# TapuinoNext-Micro.net
KiCad netlist of a schematic drawn in EAGLE
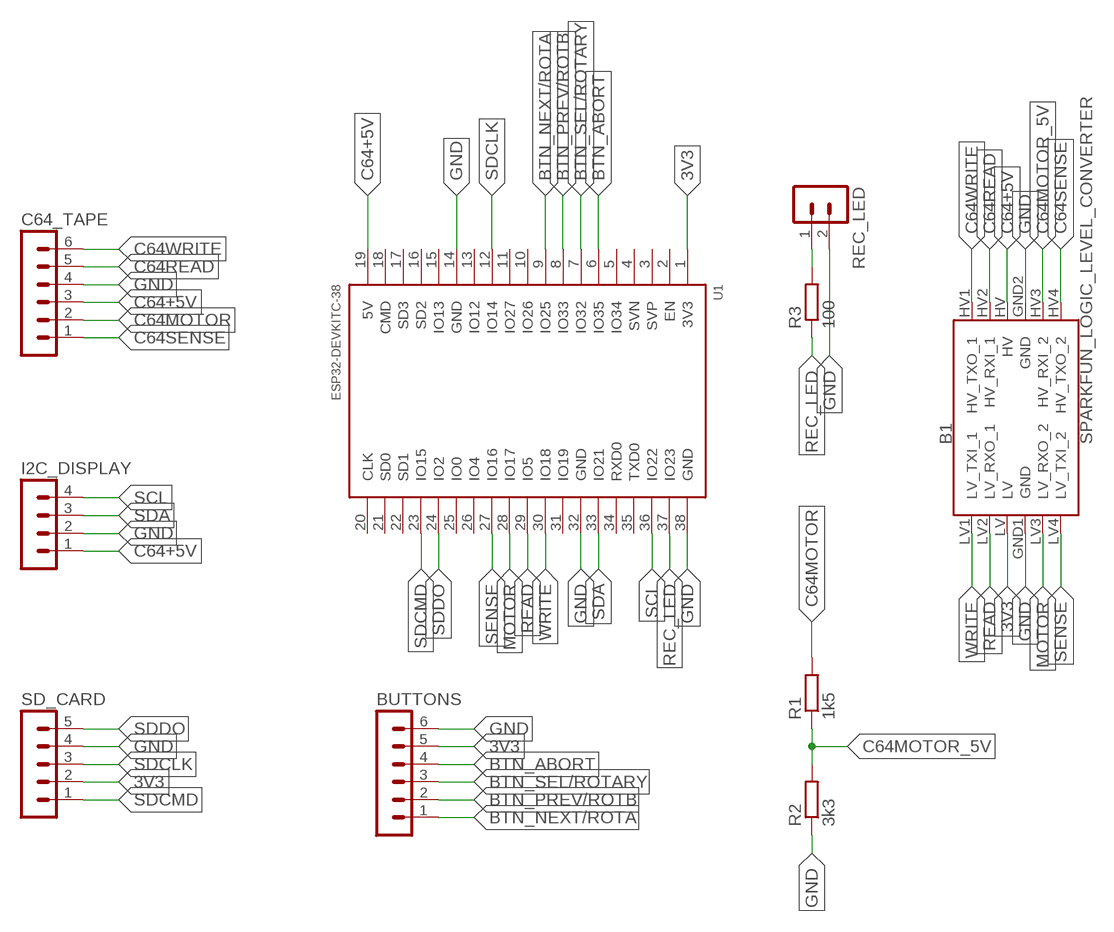
[diagram p0: schematic, sheet 1]

(export (version "E")
  (design (tool "Eeschema 10.0.6"))
  (components
    (comp (ref "B1")
      (value "SPARKFUN_LOGIC_LEVEL_CONVERTER")
      (footprint "eagle-import:SPARKFUN_LOGIC_LEVEL_CONVERTER")
      (libsource (lib "eagle-import") (part "SPARKFUN_LOGIC_LEVEL_CONVERTER"))
    )
    (comp (ref "BUTTONS")
      (value "MA06-1")
      (footprint "eagle-import:MA06-1")
      (libsource (lib "eagle-import") (part "MA06-1"))
    )
    (comp (ref "C64_TAPE")
      (value "MA06-1")
      (footprint "eagle-import:MA06-1")
      (libsource (lib "eagle-import") (part "MA06-1"))
    )
    (comp (ref "I2C_DISPLAY")
      (value "MA04-1")
      (footprint "eagle-import:MA04-1")
      (libsource (lib "eagle-import") (part "MA04-1"))
    )
    (comp (ref "R1")
      (value "1k5")
      (footprint "eagle-import:M0805")
      (libsource (lib "eagle-import") (part "R-EU_M0805"))
    )
    (comp (ref "R2")
      (value "3k3")
      (footprint "eagle-import:M0805")
      (libsource (lib "eagle-import") (part "R-EU_M0805"))
    )
    (comp (ref "R3")
      (value "100")
      (footprint "eagle-import:M0805")
      (libsource (lib "eagle-import") (part "R-EU_M0805"))
    )
    (comp (ref "REC_LED")
      (value "MA02-1")
      (footprint "eagle-import:MA02-1")
      (libsource (lib "eagle-import") (part "MA02-1"))
    )
    (comp (ref "SD_CARD")
      (value "MA05-1")
      (footprint "eagle-import:MA05-1")
      (libsource (lib "eagle-import") (part "MA05-1"))
    )
    (comp (ref "U1")
      (value "ESP32-DEVKITC-38")
      (footprint "eagle-import:ESP32-DEVKITC-38")
      (fields (field (name "AUTHOR") "SWEETLILMRE"))
      (libsource (lib "eagle-import") (part "ESP32-DEVKITC-38"))
    )
  )
  (nets
    (net (code "1") (name "3V3") (class "Default")
      (node (ref "B1") (pin "LV") (pinfunction "LV_LV") (pintype "power_in"))
      (node (ref "BUTTONS") (pin "5") (pinfunction "5_5") (pintype "passive"))
      (node (ref "SD_CARD") (pin "2") (pinfunction "2_2") (pintype "passive"))
      (node (ref "U1") (pin "1") (pinfunction "3V3_1") (pintype "power_in"))
    )
    (net (code "2") (name "BTN_ABORT") (class "Default")
      (node (ref "BUTTONS") (pin "4") (pinfunction "4_4") (pintype "passive"))
      (node (ref "U1") (pin "6") (pinfunction "IO35_6") (pintype "input"))
    )
    (net (code "3") (name "BTN_NEXT{slash}ROTA") (class "Default")
      (node (ref "BUTTONS") (pin "1") (pinfunction "1_1") (pintype "passive"))
      (node (ref "U1") (pin "9") (pinfunction "IO25_9") (pintype "bidirectional"))
    )
    (net (code "4") (name "BTN_PREV{slash}ROTB") (class "Default")
      (node (ref "BUTTONS") (pin "2") (pinfunction "2_2") (pintype "passive"))
      (node (ref "U1") (pin "8") (pinfunction "IO33_8") (pintype "bidirectional"))
    )
    (net (code "5") (name "BTN_SEL{slash}ROTARY") (class "Default")
      (node (ref "BUTTONS") (pin "3") (pinfunction "3_3") (pintype "passive"))
      (node (ref "U1") (pin "7") (pinfunction "IO32_7") (pintype "bidirectional"))
    )
    (net (code "6") (name "C64+5V") (class "Default")
      (node (ref "B1") (pin "HV") (pinfunction "HV_HV") (pintype "power_in"))
      (node (ref "C64_TAPE") (pin "3") (pinfunction "3_3") (pintype "passive"))
      (node (ref "I2C_DISPLAY") (pin "1") (pinfunction "1_1") (pintype "passive"))
      (node (ref "U1") (pin "19") (pinfunction "5V_19") (pintype "power_in"))
    )
    (net (code "7") (name "C64MOTOR") (class "Default")
      (node (ref "C64_TAPE") (pin "2") (pinfunction "2_2") (pintype "passive"))
      (node (ref "R1") (pin "2") (pinfunction "2_2") (pintype "passive"))
    )
    (net (code "8") (name "C64MOTOR_5V") (class "Default")
      (node (ref "B1") (pin "HV3") (pinfunction "HV_RXI_2_HV3") (pintype "bidirectional"))
      (node (ref "R1") (pin "1") (pinfunction "1_1") (pintype "passive"))
      (node (ref "R2") (pin "2") (pinfunction "2_2") (pintype "passive"))
    )
    (net (code "9") (name "C64READ") (class "Default")
      (node (ref "B1") (pin "HV2") (pinfunction "HV_RXI_1_HV2") (pintype "bidirectional"))
      (node (ref "C64_TAPE") (pin "5") (pinfunction "5_5") (pintype "passive"))
    )
    (net (code "10") (name "C64SENSE") (class "Default")
      (node (ref "B1") (pin "HV4") (pinfunction "HV_TXO_2_HV4") (pintype "bidirectional"))
      (node (ref "C64_TAPE") (pin "1") (pinfunction "1_1") (pintype "passive"))
    )
    (net (code "11") (name "C64WRITE") (class "Default")
      (node (ref "B1") (pin "HV1") (pinfunction "HV_TXO_1_HV1") (pintype "bidirectional"))
      (node (ref "C64_TAPE") (pin "6") (pinfunction "6_6") (pintype "passive"))
    )
    (net (code "12") (name "GND") (class "Default")
      (node (ref "B1") (pin "GND1") (pinfunction "GND_GND1") (pintype "power_in"))
      (node (ref "B1") (pin "GND2") (pinfunction "GND_GND2") (pintype "power_in"))
      (node (ref "BUTTONS") (pin "6") (pinfunction "6_6") (pintype "passive"))
      (node (ref "C64_TAPE") (pin "4") (pinfunction "4_4") (pintype "passive"))
      (node (ref "I2C_DISPLAY") (pin "2") (pinfunction "2_2") (pintype "passive"))
      (node (ref "R2") (pin "1") (pinfunction "1_1") (pintype "passive"))
      (node (ref "REC_LED") (pin "2") (pinfunction "2_2") (pintype "passive"))
      (node (ref "SD_CARD") (pin "4") (pinfunction "4_4") (pintype "passive"))
      (node (ref "U1") (pin "14") (pinfunction "GND_14") (pintype "power_in"))
      (node (ref "U1") (pin "32") (pinfunction "GND_32") (pintype "power_in"))
      (node (ref "U1") (pin "38") (pinfunction "GND_38") (pintype "power_in"))
    )
    (net (code "13") (name "MOTOR") (class "Default")
      (node (ref "B1") (pin "LV3") (pinfunction "LV_RXO_2_LV3") (pintype "bidirectional"))
      (node (ref "U1") (pin "28") (pinfunction "IO17_28") (pintype "bidirectional"))
    )
    (net (code "14") (name "Net-(R3-Pad2)") (class "Default")
      (node (ref "R3") (pin "2") (pinfunction "2_2") (pintype "passive"))
      (node (ref "REC_LED") (pin "1") (pinfunction "1_1") (pintype "passive"))
    )
    (net (code "15") (name "READ") (class "Default")
      (node (ref "B1") (pin "LV2") (pinfunction "LV_RXO_1_LV2") (pintype "bidirectional"))
      (node (ref "U1") (pin "29") (pinfunction "IO5_29") (pintype "bidirectional"))
    )
    (net (code "16") (name "REC_LED") (class "Default")
      (node (ref "R3") (pin "1") (pinfunction "1_1") (pintype "passive"))
      (node (ref "U1") (pin "37") (pinfunction "IO23_37") (pintype "bidirectional"))
    )
    (net (code "17") (name "SCL") (class "Default")
      (node (ref "I2C_DISPLAY") (pin "4") (pinfunction "4_4") (pintype "passive"))
      (node (ref "U1") (pin "36") (pinfunction "IO22_36") (pintype "bidirectional"))
    )
    (net (code "18") (name "SDA") (class "Default")
      (node (ref "I2C_DISPLAY") (pin "3") (pinfunction "3_3") (pintype "passive"))
      (node (ref "U1") (pin "33") (pinfunction "IO21_33") (pintype "bidirectional"))
    )
    (net (code "19") (name "SDCLK") (class "Default")
      (node (ref "SD_CARD") (pin "3") (pinfunction "3_3") (pintype "passive"))
      (node (ref "U1") (pin "12") (pinfunction "IO14_12") (pintype "bidirectional"))
    )
    (net (code "20") (name "SDCMD") (class "Default")
      (node (ref "SD_CARD") (pin "1") (pinfunction "1_1") (pintype "passive"))
      (node (ref "U1") (pin "23") (pinfunction "IO15_23") (pintype "bidirectional"))
    )
    (net (code "21") (name "SDDO") (class "Default")
      (node (ref "SD_CARD") (pin "5") (pinfunction "5_5") (pintype "passive"))
      (node (ref "U1") (pin "24") (pinfunction "IO2_24") (pintype "bidirectional"))
    )
    (net (code "22") (name "SENSE") (class "Default")
      (node (ref "B1") (pin "LV4") (pinfunction "LV_TXI_2_LV4") (pintype "bidirectional"))
      (node (ref "U1") (pin "27") (pinfunction "IO16_27") (pintype "bidirectional"))
    )
    (net (code "23") (name "WRITE") (class "Default")
      (node (ref "B1") (pin "LV1") (pinfunction "LV_TXI_1_LV1") (pintype "bidirectional"))
      (node (ref "U1") (pin "30") (pinfunction "IO18_30") (pintype "bidirectional"))
    )
    (net (code "24") (name "unconnected-(U1-CLK-Pad20)") (class "Default")
      (node (ref "U1") (pin "20") (pinfunction "CLK_20") (pintype "bidirectional"))
    )
    (net (code "25") (name "unconnected-(U1-CMD-Pad18)") (class "Default")
      (node (ref "U1") (pin "18") (pinfunction "CMD_18") (pintype "bidirectional"))
    )
    (net (code "26") (name "unconnected-(U1-EN-Pad2)") (class "Default")
      (node (ref "U1") (pin "2") (pinfunction "EN_2") (pintype "bidirectional"))
    )
    (net (code "27") (name "unconnected-(U1-IO0-Pad25)") (class "Default")
      (node (ref "U1") (pin "25") (pinfunction "IO0_25") (pintype "bidirectional"))
    )
    (net (code "28") (name "unconnected-(U1-IO4-Pad26)") (class "Default")
      (node (ref "U1") (pin "26") (pinfunction "IO4_26") (pintype "bidirectional"))
    )
    (net (code "29") (name "unconnected-(U1-IO12-Pad13)") (class "Default")
      (node (ref "U1") (pin "13") (pinfunction "IO12_13") (pintype "bidirectional"))
    )
    (net (code "30") (name "unconnected-(U1-IO13-Pad15)") (class "Default")
      (node (ref "U1") (pin "15") (pinfunction "IO13_15") (pintype "bidirectional"))
    )
    (net (code "31") (name "unconnected-(U1-IO19-Pad31)") (class "Default")
      (node (ref "U1") (pin "31") (pinfunction "IO19_31") (pintype "bidirectional"))
    )
    (net (code "32") (name "unconnected-(U1-IO26-Pad10)") (class "Default")
      (node (ref "U1") (pin "10") (pinfunction "IO26_10") (pintype "bidirectional"))
    )
    (net (code "33") (name "unconnected-(U1-IO27-Pad11)") (class "Default")
      (node (ref "U1") (pin "11") (pinfunction "IO27_11") (pintype "bidirectional"))
    )
    (net (code "34") (name "unconnected-(U1-IO34-Pad5)") (class "Default")
      (node (ref "U1") (pin "5") (pinfunction "IO34_5") (pintype "input"))
    )
    (net (code "35") (name "unconnected-(U1-RXD0-Pad34)") (class "Default")
      (node (ref "U1") (pin "34") (pinfunction "RXD0_34") (pintype "bidirectional"))
    )
    (net (code "36") (name "unconnected-(U1-SD0-Pad21)") (class "Default")
      (node (ref "U1") (pin "21") (pinfunction "SD0_21") (pintype "bidirectional"))
    )
    (net (code "37") (name "unconnected-(U1-SD1-Pad22)") (class "Default")
      (node (ref "U1") (pin "22") (pinfunction "SD1_22") (pintype "bidirectional"))
    )
    (net (code "38") (name "unconnected-(U1-SD2-Pad16)") (class "Default")
      (node (ref "U1") (pin "16") (pinfunction "SD2_16") (pintype "bidirectional"))
    )
    (net (code "39") (name "unconnected-(U1-SD3-Pad17)") (class "Default")
      (node (ref "U1") (pin "17") (pinfunction "SD3_17") (pintype "bidirectional"))
    )
    (net (code "40") (name "unconnected-(U1-SVN-Pad4)") (class "Default")
      (node (ref "U1") (pin "4") (pinfunction "SVN_4") (pintype "input"))
    )
    (net (code "41") (name "unconnected-(U1-SVP-Pad3)") (class "Default")
      (node (ref "U1") (pin "3") (pinfunction "SVP_3") (pintype "input"))
    )
    (net (code "42") (name "unconnected-(U1-TXD0-Pad35)") (class "Default")
      (node (ref "U1") (pin "35") (pinfunction "TXD0_35") (pintype "bidirectional"))
    )
  )
)
